# senseBox-CAM-M8Q_v20.net
KiCad netlist of a schematic drawn in EAGLE
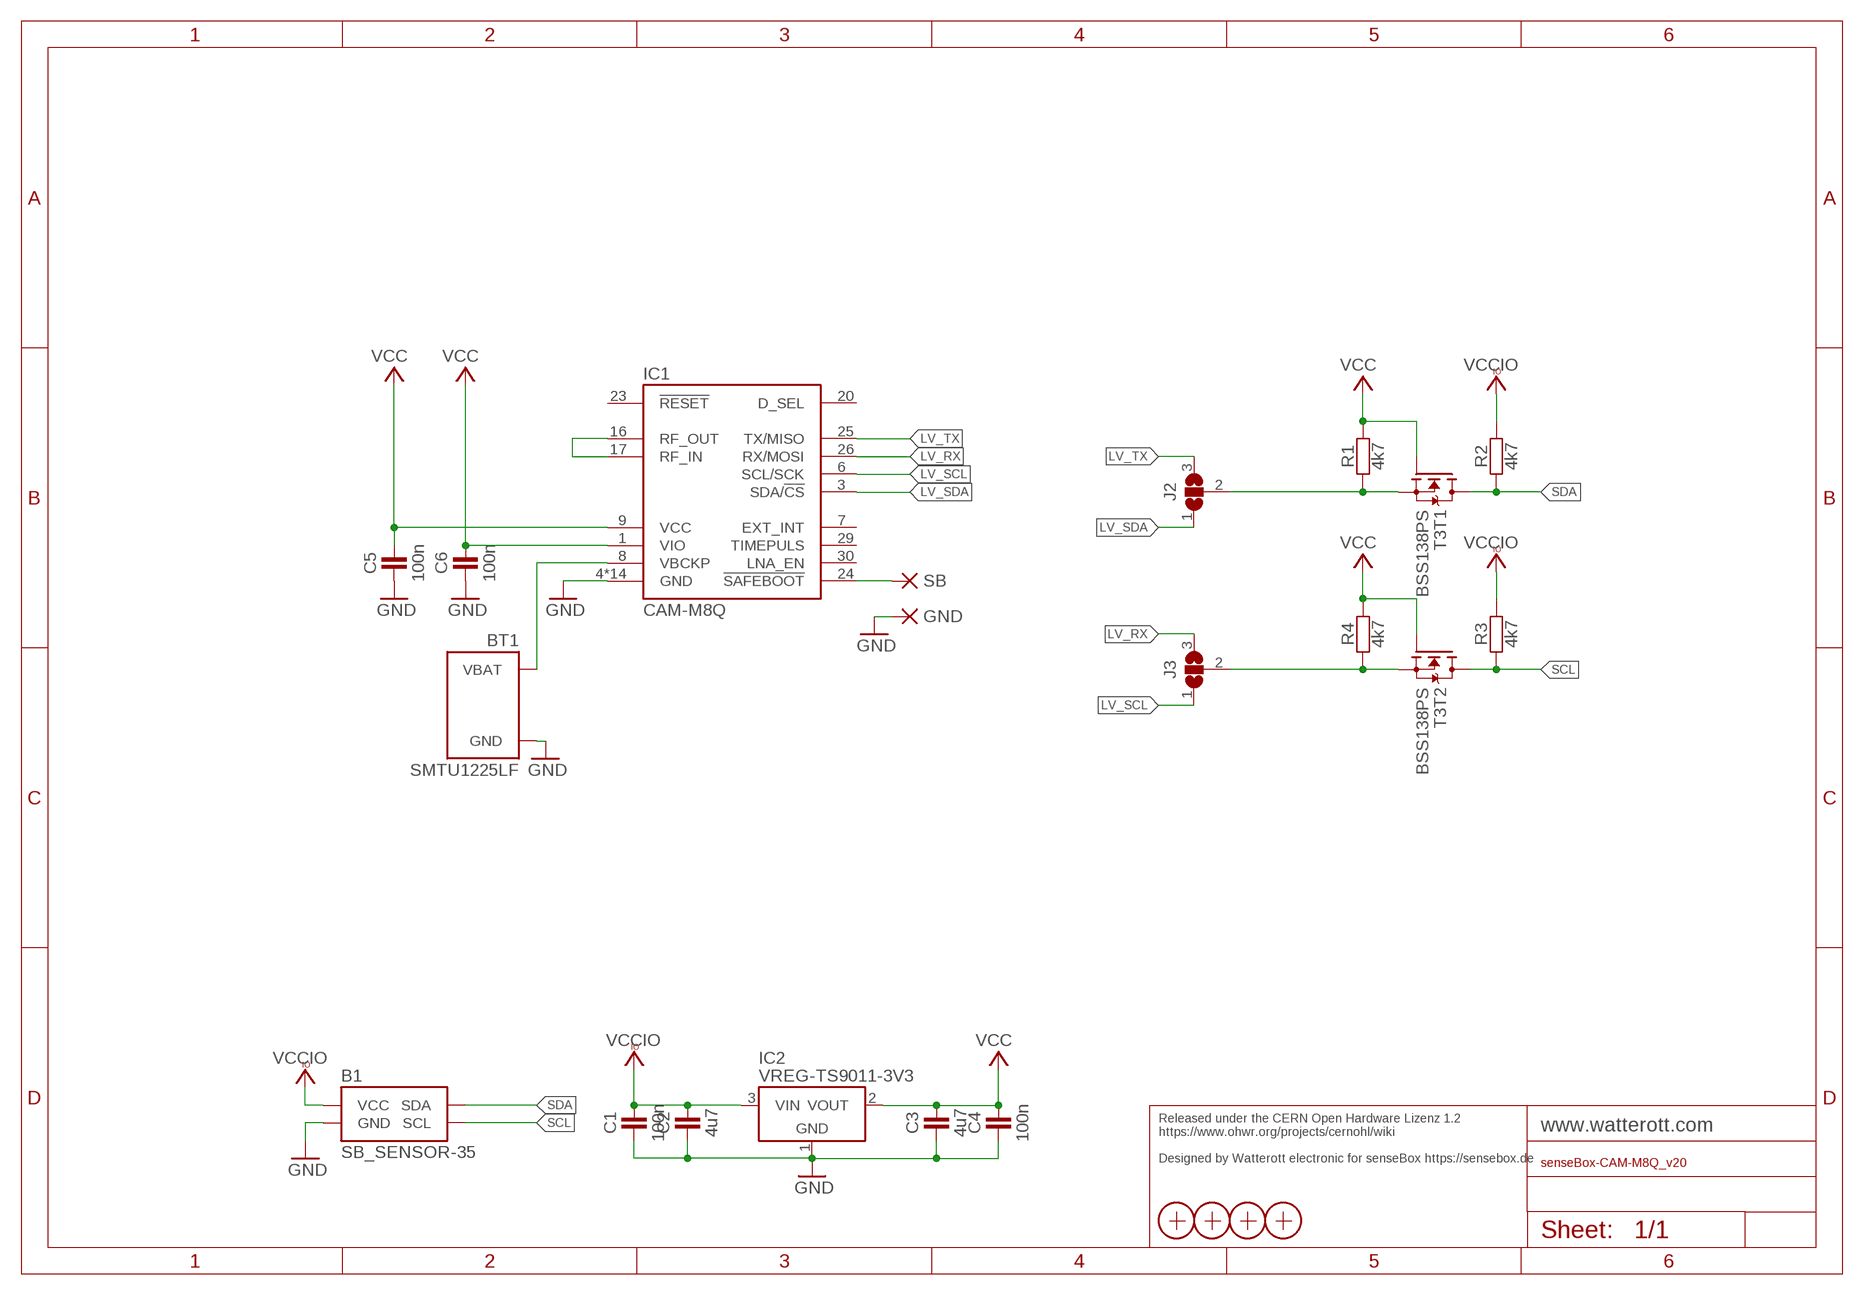
[diagram p0: schematic, sheet 1]

(export (version "E")
  (design (tool "Eeschema 10.0.6"))
  (components
    (comp (ref "B1")
      (value "SB_SENSOR-35")
      (footprint "eagle-import:SB-35X25")
      (libsource (lib "eagle-import") (part "SB_SENSOR-35"))
    )
    (comp (ref "BT1")
      (value "SMTU1225LF")
      (footprint "eagle-import:BAT-SMTU1225LF")
      (libsource (lib "eagle-import") (part "BATTERY-SMTU1225LF"))
    )
    (comp (ref "C1")
      (value "100n")
      (footprint "eagle-import:C0402")
      (libsource (lib "eagle-import") (part "CAPACITOR-0402"))
    )
    (comp (ref "C2")
      (value "4u7")
      (footprint "eagle-import:C0402")
      (libsource (lib "eagle-import") (part "CAPACITOR-0402"))
    )
    (comp (ref "C3")
      (value "4u7")
      (footprint "eagle-import:C0402")
      (libsource (lib "eagle-import") (part "CAPACITOR-0402"))
    )
    (comp (ref "C4")
      (value "100n")
      (footprint "eagle-import:C0402")
      (libsource (lib "eagle-import") (part "CAPACITOR-0402"))
    )
    (comp (ref "C5")
      (value "100n")
      (footprint "eagle-import:C0402")
      (libsource (lib "eagle-import") (part "CAPACITOR-0402"))
    )
    (comp (ref "C6")
      (value "100n")
      (footprint "eagle-import:C0402")
      (libsource (lib "eagle-import") (part "CAPACITOR-0402"))
    )
    (comp (ref "GND")
      (value "PAD-1.27X1.27_NC")
      (footprint "eagle-import:PAD-1.27X1.27_NC")
      (libsource (lib "eagle-import") (part "PAD-1.27X1.27_NC"))
    )
    (comp (ref "IC1")
      (value "CAM-M8Q")
      (footprint "eagle-import:CAM-M8Q")
      (libsource (lib "eagle-import") (part "CAM-M8Q"))
    )
    (comp (ref "IC2")
      (value "VREG-TS9011-3V3")
      (footprint "eagle-import:SOT23")
      (libsource (lib "eagle-import") (part "VREG-TS9011-3V3"))
    )
    (comp (ref "J2")
      (value "JUMPER3-0603-NC")
      (footprint "eagle-import:JUMPER3-0603_NC")
      (libsource (lib "eagle-import") (part "JUMPER3-0603-NC"))
    )
    (comp (ref "J3")
      (value "JUMPER3-0603-NC")
      (footprint "eagle-import:JUMPER3-0603_NC")
      (libsource (lib "eagle-import") (part "JUMPER3-0603-NC"))
    )
    (comp (ref "R1")
      (value "4k7")
      (footprint "eagle-import:C0402")
      (libsource (lib "eagle-import") (part "RESISTOR-0402"))
    )
    (comp (ref "R2")
      (value "4k7")
      (footprint "eagle-import:C0402")
      (libsource (lib "eagle-import") (part "RESISTOR-0402"))
    )
    (comp (ref "R3")
      (value "4k7")
      (footprint "eagle-import:C0402")
      (libsource (lib "eagle-import") (part "RESISTOR-0402"))
    )
    (comp (ref "R4")
      (value "4k7")
      (footprint "eagle-import:C0402")
      (libsource (lib "eagle-import") (part "RESISTOR-0402"))
    )
    (comp (ref "SB")
      (value "PAD-1.27X1.27_NC")
      (footprint "eagle-import:PAD-1.27X1.27_NC")
      (libsource (lib "eagle-import") (part "PAD-1.27X1.27_NC"))
    )
    (comp (ref "T3")
      (value "BSS138PS")
      (footprint "eagle-import:SOT363")
      (libsource (lib "eagle-import") (part "BSS138PS"))
    )
    (comp (ref "X1")
      (value "PASSER-07")
      (footprint "eagle-import:PASSER_07MM")
      (libsource (lib "eagle-import") (part "PASSER-07"))
    )
    (comp (ref "X2")
      (value "PASSER-07")
      (footprint "eagle-import:PASSER_07MM")
      (libsource (lib "eagle-import") (part "PASSER-07"))
    )
    (comp (ref "X3")
      (value "PASSER-07")
      (footprint "eagle-import:PASSER_07MM")
      (libsource (lib "eagle-import") (part "PASSER-07"))
    )
    (comp (ref "X4")
      (value "PASSER-07")
      (footprint "eagle-import:PASSER_07MM")
      (libsource (lib "eagle-import") (part "PASSER-07"))
    )
  )
  (nets
    (net (code "1") (name "GND") (class "Default")
      (node (ref "B1") (pin "GND") (pinfunction "GND_GND") (pintype "power_in"))
      (node (ref "BT1") (pin "-") (pinfunction "GND_-") (pintype "power_in"))
      (node (ref "C1") (pin "1") (pinfunction "1_1") (pintype "passive"))
      (node (ref "C2") (pin "1") (pinfunction "1_1") (pintype "passive"))
      (node (ref "C3") (pin "1") (pinfunction "1_1") (pintype "passive"))
      (node (ref "C4") (pin "1") (pinfunction "1_1") (pintype "passive"))
      (node (ref "C5") (pin "1") (pinfunction "1_1") (pintype "passive"))
      (node (ref "C6") (pin "1") (pinfunction "1_1") (pintype "passive"))
      (node (ref "GND") (pin "1") (pinfunction "P_1") (pintype "passive"))
      (node (ref "IC1") (pin "10") (pinfunction "GND_10") (pintype "power_in"))
      (node (ref "IC1") (pin "11") (pinfunction "GND_11") (pintype "power_in"))
      (node (ref "IC1") (pin "12") (pinfunction "GND_12") (pintype "power_in"))
      (node (ref "IC1") (pin "13") (pinfunction "GND_13") (pintype "power_in"))
      (node (ref "IC1") (pin "14") (pinfunction "GND_14") (pintype "power_in"))
      (node (ref "IC1") (pin "15") (pinfunction "GND_15") (pintype "power_in"))
      (node (ref "IC1") (pin "18") (pinfunction "GND_18") (pintype "power_in"))
      (node (ref "IC1") (pin "19") (pinfunction "GND_19") (pintype "power_in"))
      (node (ref "IC1") (pin "21") (pinfunction "GND_21") (pintype "power_in"))
      (node (ref "IC1") (pin "22") (pinfunction "GND_22") (pintype "power_in"))
      (node (ref "IC1") (pin "27") (pinfunction "GND_27") (pintype "power_in"))
      (node (ref "IC1") (pin "31") (pinfunction "GND_31") (pintype "power_in"))
      (node (ref "IC1") (pin "4") (pinfunction "GND_4") (pintype "power_in"))
      (node (ref "IC1") (pin "5") (pinfunction "GND_5") (pintype "power_in"))
      (node (ref "IC2") (pin "1") (pinfunction "GND_1") (pintype "power_in"))
    )
    (net (code "2") (name "LV_RX") (class "Default")
      (node (ref "IC1") (pin "26") (pinfunction "RX/MOSI_26") (pintype "input"))
      (node (ref "J3") (pin "3") (pinfunction "3_3") (pintype "passive"))
    )
    (net (code "3") (name "LV_SCL") (class "Default")
      (node (ref "IC1") (pin "6") (pinfunction "SCL/SCK_6") (pintype "bidirectional"))
      (node (ref "J3") (pin "1") (pinfunction "1_1") (pintype "passive"))
    )
    (net (code "4") (name "LV_SDA") (class "Default")
      (node (ref "IC1") (pin "3") (pinfunction "SDA/~{CS}_3") (pintype "bidirectional"))
      (node (ref "J2") (pin "1") (pinfunction "1_1") (pintype "passive"))
    )
    (net (code "5") (name "LV_TX") (class "Default")
      (node (ref "IC1") (pin "25") (pinfunction "TX/MISO_25") (pintype "output"))
      (node (ref "J2") (pin "3") (pinfunction "3_3") (pintype "passive"))
    )
    (net (code "6") (name "Net-(BT1-VBAT)") (class "Default")
      (node (ref "BT1") (pin "+") (pinfunction "VBAT_+") (pintype "power_in"))
      (node (ref "IC1") (pin "8") (pinfunction "VBCKP_8") (pintype "power_in"))
    )
    (net (code "7") (name "Net-(IC1-RF_IN)") (class "Default")
      (node (ref "IC1") (pin "16") (pinfunction "RF_OUT_16") (pintype "output"))
      (node (ref "IC1") (pin "17") (pinfunction "RF_IN_17") (pintype "input"))
    )
    (net (code "8") (name "Net-(IC1-~{SAFEBOOT})") (class "Default")
      (node (ref "IC1") (pin "24") (pinfunction "~{SAFEBOOT}_24") (pintype "bidirectional"))
      (node (ref "SB") (pin "1") (pinfunction "P_1") (pintype "passive"))
    )
    (net (code "9") (name "Net-(T3A-S)") (class "Default")
      (node (ref "J2") (pin "2") (pinfunction "2_2") (pintype "passive"))
      (node (ref "R1") (pin "1") (pinfunction "1_1") (pintype "passive"))
      (node (ref "T3") (pin "1") (pinfunction "S_1") (pintype "passive"))
    )
    (net (code "10") (name "Net-(T3B-S)") (class "Default")
      (node (ref "J3") (pin "2") (pinfunction "2_2") (pintype "passive"))
      (node (ref "R4") (pin "1") (pinfunction "1_1") (pintype "passive"))
      (node (ref "T3") (pin "4") (pinfunction "S_4") (pintype "passive"))
    )
    (net (code "11") (name "SCL") (class "Default")
      (node (ref "B1") (pin "SCL") (pinfunction "SCL_SCL") (pintype "bidirectional"))
      (node (ref "R3") (pin "1") (pinfunction "1_1") (pintype "passive"))
      (node (ref "T3") (pin "3") (pinfunction "D_3") (pintype "passive"))
    )
    (net (code "12") (name "SDA") (class "Default")
      (node (ref "B1") (pin "SDA") (pinfunction "SDA_SDA") (pintype "bidirectional"))
      (node (ref "R2") (pin "1") (pinfunction "1_1") (pintype "passive"))
      (node (ref "T3") (pin "6") (pinfunction "D_6") (pintype "passive"))
    )
    (net (code "13") (name "VCC") (class "Default")
      (node (ref "C3") (pin "2") (pinfunction "2_2") (pintype "passive"))
      (node (ref "C4") (pin "2") (pinfunction "2_2") (pintype "passive"))
      (node (ref "C5") (pin "2") (pinfunction "2_2") (pintype "passive"))
      (node (ref "C6") (pin "2") (pinfunction "2_2") (pintype "passive"))
      (node (ref "IC1") (pin "1") (pinfunction "VIO_1") (pintype "power_in"))
      (node (ref "IC1") (pin "9") (pinfunction "VCC_9") (pintype "power_in"))
      (node (ref "IC2") (pin "2") (pinfunction "VOUT_2") (pintype "power_in"))
      (node (ref "R1") (pin "2") (pinfunction "2_2") (pintype "passive"))
      (node (ref "R4") (pin "2") (pinfunction "2_2") (pintype "passive"))
      (node (ref "T3") (pin "2") (pinfunction "G_2") (pintype "passive"))
      (node (ref "T3") (pin "5") (pinfunction "G_5") (pintype "passive"))
    )
    (net (code "14") (name "VCCIO") (class "Default")
      (node (ref "B1") (pin "VCC") (pinfunction "VCC_VCC") (pintype "power_in"))
      (node (ref "C1") (pin "2") (pinfunction "2_2") (pintype "passive"))
      (node (ref "C2") (pin "2") (pinfunction "2_2") (pintype "passive"))
      (node (ref "IC2") (pin "3") (pinfunction "VIN_3") (pintype "power_in"))
      (node (ref "R2") (pin "2") (pinfunction "2_2") (pintype "passive"))
      (node (ref "R3") (pin "2") (pinfunction "2_2") (pintype "passive"))
    )
    (net (code "15") (name "unconnected-(IC1-D_SEL-Pad20)") (class "Default")
      (node (ref "IC1") (pin "20") (pinfunction "D_SEL_20") (pintype "bidirectional"))
    )
    (net (code "16") (name "unconnected-(IC1-EXT_INT-Pad7)") (class "Default")
      (node (ref "IC1") (pin "7") (pinfunction "EXT_INT_7") (pintype "bidirectional"))
    )
    (net (code "17") (name "unconnected-(IC1-LNA_EN-Pad30)") (class "Default")
      (node (ref "IC1") (pin "30") (pinfunction "LNA_EN_30") (pintype "bidirectional"))
    )
    (net (code "18") (name "unconnected-(IC1-TIMEPULS-Pad29)") (class "Default")
      (node (ref "IC1") (pin "29") (pinfunction "TIMEPULS_29") (pintype "output"))
    )
    (net (code "19") (name "unconnected-(IC1-~{RESET}-Pad23)") (class "Default")
      (node (ref "IC1") (pin "23") (pinfunction "~{RESET}_23") (pintype "input"))
    )
  )
)
